# SCH_Endurance_drone_3.net
KiCad netlist of a schematic drawn in EasyEDA
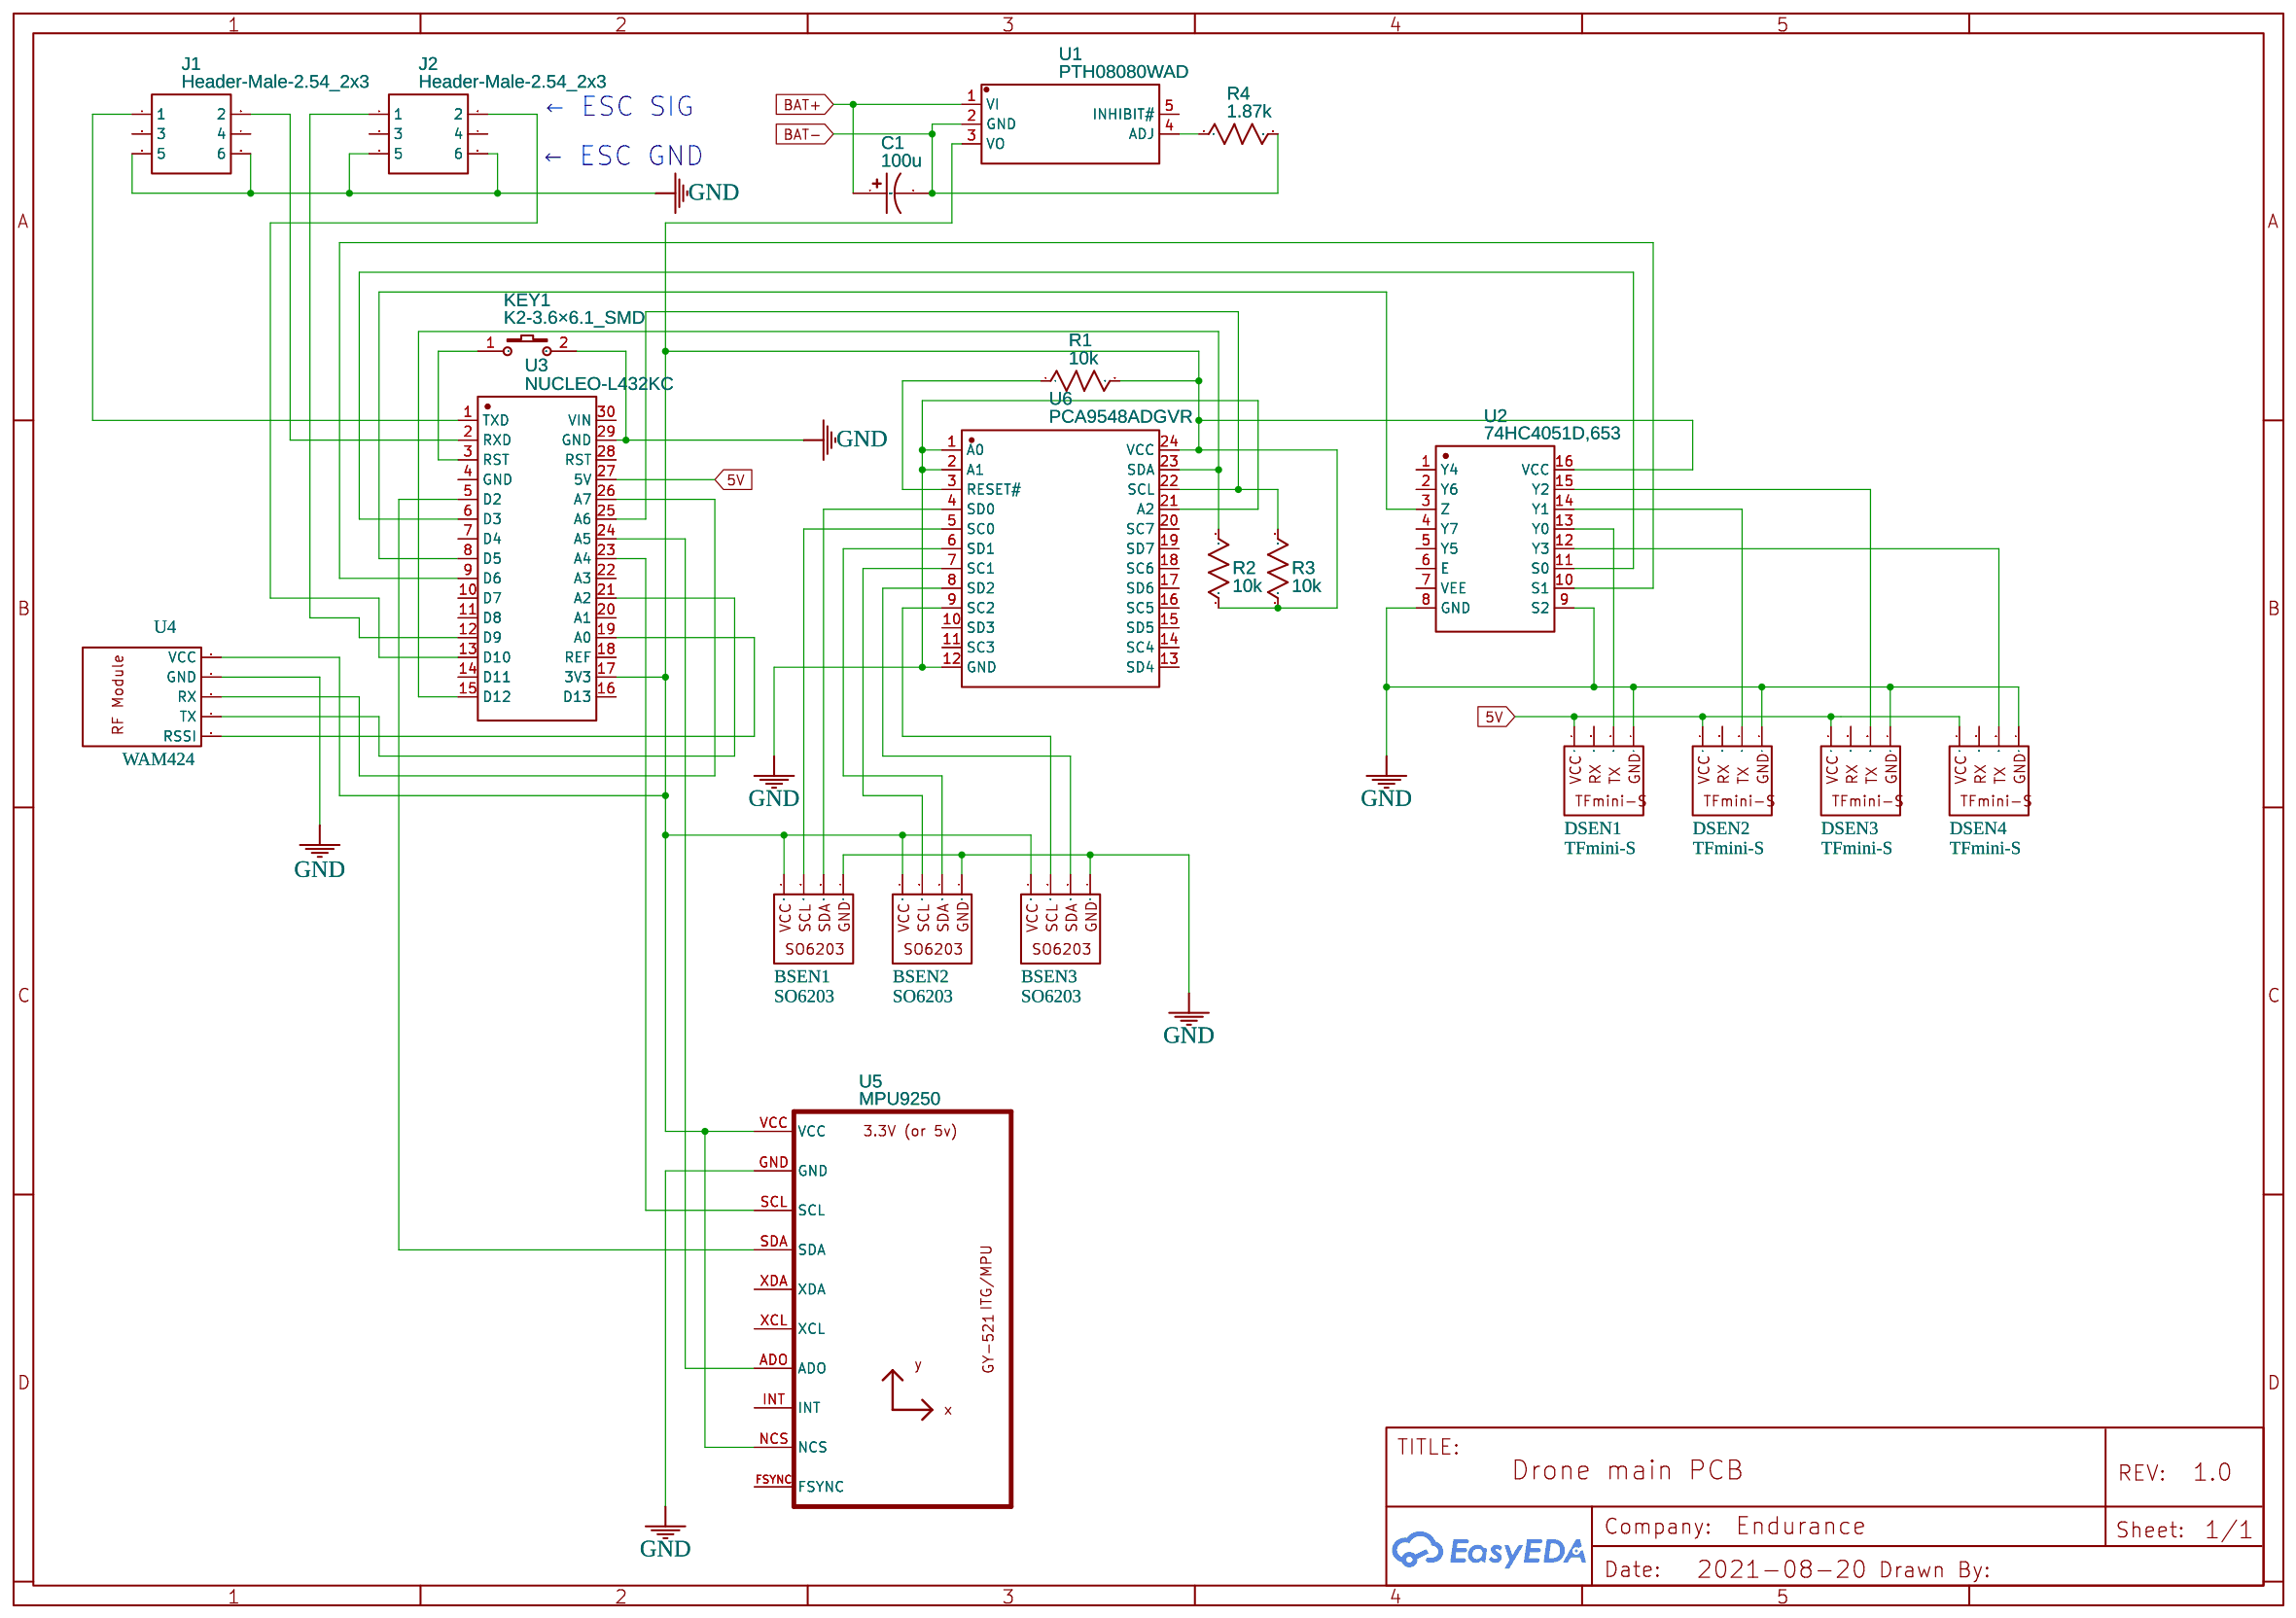
[diagram p0: schematic sheet]

(export (version "E")
  (design (tool "Eeschema 10.0.6"))
  (components
    (comp (ref "BSEN1") (value "SO6203") (libsource (lib "") (part "Unknown_405_-350")))
    (comp (ref "BSEN2") (value "SO6203") (libsource (lib "") (part "Unknown_465_-350")))
    (comp (ref "BSEN3") (value "SO6203") (libsource (lib "") (part "Unknown_530_-350")))
    (comp (ref "C1") (value "100u") (libsource (lib "") (part "C_Tan_SMD_A_US")))
    (comp (ref "DSEN1") (value "TFmini-S") (libsource (lib "") (part "Unknown_805_-425")))
    (comp (ref "DSEN2") (value "TFmini-S") (libsource (lib "") (part "Unknown_870_-425")))
    (comp (ref "DSEN3") (value "TFmini-S") (libsource (lib "") (part "Unknown_935_-425")))
    (comp (ref "DSEN4") (value "TFmini-S") (libsource (lib "") (part "Unknown_1000_-425")))
    (comp (ref "J1")
      (value "Header-Male-2.54_2x3")
      (fields (field (name "BOM_Supplier Part") "C65114"))
      (libsource (lib "") (part "Header-Male-2.54_2x3"))
    )
    (comp (ref "J2")
      (value "Header-Male-2.54_2x3")
      (fields (field (name "BOM_Supplier Part") "C65114"))
      (libsource (lib "") (part "Header-Male-2.54_2x3"))
    )
    (comp (ref "KEY1")
      (value "K2-3.6×6.1_SMD")
      (fields
        (field (name "BOM_Manufacturer Part") "K2-1107ST-A4SW-06")
        (field (name "BOM_Supplier Part") "C118141")
      )
      (libsource (lib "") (part "K2-3.6×6.1_SMD"))
    )
    (comp (ref "R1") (value "10k") (libsource (lib "") (part "R_0603_US_1")))
    (comp (ref "R2") (value "10k") (libsource (lib "") (part "R_0603_US")))
    (comp (ref "R3") (value "10k") (libsource (lib "") (part "R_0603_US")))
    (comp (ref "R4") (value "1.87k") (libsource (lib "") (part "R_0603_US_1")))
    (comp (ref "U1")
      (value "PTH08080WAD")
      (fields (field (name "BOM_Supplier Part") "C154927"))
      (libsource (lib "") (part "PTH08080WAD"))
    )
    (comp (ref "U2")
      (value "74HC4051D,653")
      (fields (field (name "BOM_Supplier Part") "C9386"))
      (libsource (lib "") (part "74HC4051D,653"))
    )
    (comp (ref "U3")
      (value "NUCLEO-L432KC")
      (fields (field (name "BOM_Supplier Part") "C94814"))
      (libsource (lib "") (part "NUCLEO-L432KC"))
    )
    (comp (ref "U4") (value "WAM424") (libsource (lib "") (part "Unknown_70_-460")))
    (comp (ref "U5") (value "MPU9250") (libsource (lib "") (part "MPU9250")))
    (comp (ref "U6")
      (value "PCA9548ADGVR")
      (fields (field (name "BOM_Supplier Part") "C2674421"))
      (libsource (lib "") (part "PCA9548ADGVR"))
    )
  )
  (nets
    (net (code "1") (name "5V") (class "Default")
      (node (ref "DSEN1") (pin "1") (pinfunction "1_1") (pintype "unspecified"))
      (node (ref "DSEN2") (pin "1") (pinfunction "1_1") (pintype "unspecified"))
      (node (ref "DSEN3") (pin "1") (pinfunction "1_1") (pintype "unspecified"))
      (node (ref "DSEN4") (pin "1") (pinfunction "1_1") (pintype "unspecified"))
      (node (ref "U3") (pin "27") (pinfunction "5V_27") (pintype "unspecified"))
    )
    (net (code "2") (name "BAT+") (class "Default")
      (node (ref "C1") (pin "1") (pinfunction "1_1") (pintype "unspecified"))
      (node (ref "U1") (pin "1") (pinfunction "VI_1") (pintype "unspecified"))
    )
    (net (code "3") (name "BAT-") (class "Default")
      (node (ref "C1") (pin "2") (pinfunction "2_2") (pintype "unspecified"))
      (node (ref "R4") (pin "2") (pinfunction "2_2") (pintype "unspecified"))
      (node (ref "U1") (pin "2") (pinfunction "GND_2") (pintype "unspecified"))
    )
    (net (code "4") (name "GND") (class "Default")
      (node (ref "BSEN1") (pin "4") (pinfunction "4_4") (pintype "unspecified"))
      (node (ref "BSEN2") (pin "4") (pinfunction "4_4") (pintype "unspecified"))
      (node (ref "BSEN3") (pin "4") (pinfunction "4_4") (pintype "unspecified"))
      (node (ref "DSEN1") (pin "4") (pinfunction "4_4") (pintype "unspecified"))
      (node (ref "DSEN2") (pin "4") (pinfunction "4_4") (pintype "unspecified"))
      (node (ref "DSEN3") (pin "4") (pinfunction "4_4") (pintype "unspecified"))
      (node (ref "DSEN4") (pin "4") (pinfunction "4_4") (pintype "unspecified"))
      (node (ref "J1") (pin "5") (pinfunction "5_5") (pintype "input"))
      (node (ref "J1") (pin "6") (pinfunction "6_6") (pintype "input"))
      (node (ref "J2") (pin "5") (pinfunction "5_5") (pintype "input"))
      (node (ref "J2") (pin "6") (pinfunction "6_6") (pintype "input"))
      (node (ref "KEY1") (pin "2") (pinfunction "2_2") (pintype "unspecified"))
      (node (ref "U2") (pin "8") (pinfunction "GND_8") (pintype "unspecified"))
      (node (ref "U2") (pin "9") (pinfunction "S2_9") (pintype "unspecified"))
      (node (ref "U3") (pin "29") (pinfunction "GND_29") (pintype "unspecified"))
      (node (ref "U4") (pin "2") (pinfunction "GND_2") (pintype "unspecified"))
      (node (ref "U5") (pin "GND") (pinfunction "GND_GND") (pintype "bidirectional"))
      (node (ref "U6") (pin "1") (pinfunction "A0_1") (pintype "unspecified"))
      (node (ref "U6") (pin "12") (pinfunction "GND_12") (pintype "unspecified"))
      (node (ref "U6") (pin "2") (pinfunction "A1_2") (pintype "unspecified"))
      (node (ref "U6") (pin "21") (pinfunction "A2_21") (pintype "unspecified"))
    )
    (net (code "5") (name "Net-(KEY1-Pad1)") (class "Default")
      (node (ref "KEY1") (pin "1") (pinfunction "1_1") (pintype "unspecified"))
      (node (ref "U3") (pin "3") (pinfunction "RST_3") (pintype "unspecified"))
    )
    (net (code "6") (name "Net-(U1-ADJ)") (class "Default")
      (node (ref "R4") (pin "1") (pinfunction "1_1") (pintype "unspecified"))
      (node (ref "U1") (pin "4") (pinfunction "ADJ_4") (pintype "unspecified"))
    )
    (net (code "7") (name "Net-(U1-VO)") (class "Default")
      (node (ref "BSEN1") (pin "1") (pinfunction "1_1") (pintype "unspecified"))
      (node (ref "BSEN2") (pin "1") (pinfunction "1_1") (pintype "unspecified"))
      (node (ref "BSEN3") (pin "1") (pinfunction "1_1") (pintype "unspecified"))
      (node (ref "R1") (pin "2") (pinfunction "2_2") (pintype "unspecified"))
      (node (ref "R2") (pin "1") (pinfunction "1_1") (pintype "unspecified"))
      (node (ref "R3") (pin "1") (pinfunction "1_1") (pintype "unspecified"))
      (node (ref "U1") (pin "3") (pinfunction "VO_3") (pintype "unspecified"))
      (node (ref "U2") (pin "16") (pinfunction "VCC_16") (pintype "unspecified"))
      (node (ref "U3") (pin "17") (pinfunction "3V3_17") (pintype "unspecified"))
      (node (ref "U4") (pin "1") (pinfunction "VCC_1") (pintype "unspecified"))
      (node (ref "U5") (pin "NCS") (pinfunction "NCS_NCS") (pintype "bidirectional"))
      (node (ref "U5") (pin "VCC") (pinfunction "VCC_VCC") (pintype "bidirectional"))
      (node (ref "U6") (pin "24") (pinfunction "VCC_24") (pintype "unspecified"))
    )
    (net (code "8") (name "Net-(U2-S0)") (class "Default")
      (node (ref "U2") (pin "11") (pinfunction "S0_11") (pintype "unspecified"))
      (node (ref "U3") (pin "6") (pinfunction "D3_6") (pintype "unspecified"))
    )
    (net (code "9") (name "Net-(U2-S1)") (class "Default")
      (node (ref "U2") (pin "10") (pinfunction "S1_10") (pintype "unspecified"))
      (node (ref "U3") (pin "9") (pinfunction "D6_9") (pintype "unspecified"))
    )
    (net (code "10") (name "Net-(U2-Y0)") (class "Default")
      (node (ref "DSEN1") (pin "3") (pinfunction "3_3") (pintype "unspecified"))
      (node (ref "U2") (pin "13") (pinfunction "Y0_13") (pintype "unspecified"))
    )
    (net (code "11") (name "Net-(U2-Y1)") (class "Default")
      (node (ref "DSEN2") (pin "3") (pinfunction "3_3") (pintype "unspecified"))
      (node (ref "U2") (pin "14") (pinfunction "Y1_14") (pintype "unspecified"))
    )
    (net (code "12") (name "Net-(U2-Y2)") (class "Default")
      (node (ref "DSEN3") (pin "3") (pinfunction "3_3") (pintype "unspecified"))
      (node (ref "U2") (pin "15") (pinfunction "Y2_15") (pintype "unspecified"))
    )
    (net (code "13") (name "Net-(U2-Y3)") (class "Default")
      (node (ref "DSEN4") (pin "3") (pinfunction "3_3") (pintype "unspecified"))
      (node (ref "U2") (pin "12") (pinfunction "Y3_12") (pintype "unspecified"))
    )
    (net (code "14") (name "Net-(U2-Z)") (class "Default")
      (node (ref "U2") (pin "3") (pinfunction "Z_3") (pintype "unspecified"))
      (node (ref "U3") (pin "8") (pinfunction "D5_8") (pintype "unspecified"))
    )
    (net (code "15") (name "Net-(U3-A0)") (class "Default")
      (node (ref "U3") (pin "19") (pinfunction "A0_19") (pintype "unspecified"))
      (node (ref "U4") (pin "5") (pinfunction "RSSI_5") (pintype "unspecified"))
    )
    (net (code "16") (name "Net-(U3-A2)") (class "Default")
      (node (ref "U3") (pin "21") (pinfunction "A2_21") (pintype "unspecified"))
      (node (ref "U4") (pin "4") (pinfunction "TX_4") (pintype "unspecified"))
    )
    (net (code "17") (name "Net-(U3-A4)") (class "Default")
      (node (ref "U3") (pin "23") (pinfunction "A4_23") (pintype "unspecified"))
      (node (ref "U5") (pin "SCL") (pinfunction "SCL_SCL") (pintype "bidirectional"))
    )
    (net (code "18") (name "Net-(U3-A5)") (class "Default")
      (node (ref "U3") (pin "24") (pinfunction "A5_24") (pintype "unspecified"))
      (node (ref "U5") (pin "ADO") (pinfunction "ADO_ADO") (pintype "bidirectional"))
    )
    (net (code "19") (name "Net-(U3-A6)") (class "Default")
      (node (ref "R3") (pin "2") (pinfunction "2_2") (pintype "unspecified"))
      (node (ref "U3") (pin "25") (pinfunction "A6_25") (pintype "unspecified"))
      (node (ref "U6") (pin "22") (pinfunction "SCL_22") (pintype "unspecified"))
    )
    (net (code "20") (name "Net-(U3-A7)") (class "Default")
      (node (ref "U3") (pin "26") (pinfunction "A7_26") (pintype "unspecified"))
      (node (ref "U4") (pin "3") (pinfunction "RX_3") (pintype "unspecified"))
    )
    (net (code "21") (name "Net-(U3-D2)") (class "Default")
      (node (ref "U3") (pin "5") (pinfunction "D2_5") (pintype "unspecified"))
      (node (ref "U5") (pin "SDA") (pinfunction "SDA_SDA") (pintype "bidirectional"))
    )
    (net (code "22") (name "Net-(U3-D9)") (class "Default")
      (node (ref "J2") (pin "1") (pinfunction "1_1") (pintype "input"))
      (node (ref "U3") (pin "12") (pinfunction "D9_12") (pintype "unspecified"))
    )
    (net (code "23") (name "Net-(U3-D10)") (class "Default")
      (node (ref "J2") (pin "2") (pinfunction "2_2") (pintype "input"))
      (node (ref "U3") (pin "13") (pinfunction "D10_13") (pintype "unspecified"))
    )
    (net (code "24") (name "Net-(U3-D12)") (class "Default")
      (node (ref "R2") (pin "2") (pinfunction "2_2") (pintype "unspecified"))
      (node (ref "U3") (pin "15") (pinfunction "D12_15") (pintype "unspecified"))
      (node (ref "U6") (pin "23") (pinfunction "SDA_23") (pintype "unspecified"))
    )
    (net (code "25") (name "Net-(U3-RXD)") (class "Default")
      (node (ref "J1") (pin "2") (pinfunction "2_2") (pintype "input"))
      (node (ref "U3") (pin "2") (pinfunction "RXD_2") (pintype "unspecified"))
    )
    (net (code "26") (name "Net-(U3-TXD)") (class "Default")
      (node (ref "J1") (pin "1") (pinfunction "1_1") (pintype "input"))
      (node (ref "U3") (pin "1") (pinfunction "TXD_1") (pintype "unspecified"))
    )
    (net (code "27") (name "Net-(U6-RESET#)") (class "Default")
      (node (ref "R1") (pin "1") (pinfunction "1_1") (pintype "unspecified"))
      (node (ref "U6") (pin "3") (pinfunction "RESET#_3") (pintype "unspecified"))
    )
    (net (code "28") (name "Net-(U6-SC0)") (class "Default")
      (node (ref "BSEN1") (pin "2") (pinfunction "2_2") (pintype "unspecified"))
      (node (ref "U6") (pin "5") (pinfunction "SC0_5") (pintype "unspecified"))
    )
    (net (code "29") (name "Net-(U6-SC1)") (class "Default")
      (node (ref "BSEN2") (pin "2") (pinfunction "2_2") (pintype "unspecified"))
      (node (ref "U6") (pin "7") (pinfunction "SC1_7") (pintype "unspecified"))
    )
    (net (code "30") (name "Net-(U6-SC2)") (class "Default")
      (node (ref "BSEN3") (pin "2") (pinfunction "2_2") (pintype "unspecified"))
      (node (ref "U6") (pin "9") (pinfunction "SC2_9") (pintype "unspecified"))
    )
    (net (code "31") (name "Net-(U6-SD0)") (class "Default")
      (node (ref "BSEN1") (pin "3") (pinfunction "3_3") (pintype "unspecified"))
      (node (ref "U6") (pin "4") (pinfunction "SD0_4") (pintype "unspecified"))
    )
    (net (code "32") (name "Net-(U6-SD1)") (class "Default")
      (node (ref "BSEN2") (pin "3") (pinfunction "3_3") (pintype "unspecified"))
      (node (ref "U6") (pin "6") (pinfunction "SD1_6") (pintype "unspecified"))
    )
    (net (code "33") (name "Net-(U6-SD2)") (class "Default")
      (node (ref "BSEN3") (pin "3") (pinfunction "3_3") (pintype "unspecified"))
      (node (ref "U6") (pin "8") (pinfunction "SD2_8") (pintype "unspecified"))
    )
    (net (code "34") (name "unconnected-(DSEN1-Pad2)") (class "Default")
      (node (ref "DSEN1") (pin "2") (pinfunction "2_2") (pintype "unspecified"))
    )
    (net (code "35") (name "unconnected-(DSEN2-Pad2)") (class "Default")
      (node (ref "DSEN2") (pin "2") (pinfunction "2_2") (pintype "unspecified"))
    )
    (net (code "36") (name "unconnected-(DSEN3-Pad2)") (class "Default")
      (node (ref "DSEN3") (pin "2") (pinfunction "2_2") (pintype "unspecified"))
    )
    (net (code "37") (name "unconnected-(DSEN4-Pad2)") (class "Default")
      (node (ref "DSEN4") (pin "2") (pinfunction "2_2") (pintype "unspecified"))
    )
    (net (code "38") (name "unconnected-(J1-Pad3)") (class "Default")
      (node (ref "J1") (pin "3") (pinfunction "3_3") (pintype "input"))
    )
    (net (code "39") (name "unconnected-(J1-Pad4)") (class "Default")
      (node (ref "J1") (pin "4") (pinfunction "4_4") (pintype "input"))
    )
    (net (code "40") (name "unconnected-(J2-Pad3)") (class "Default")
      (node (ref "J2") (pin "3") (pinfunction "3_3") (pintype "input"))
    )
    (net (code "41") (name "unconnected-(J2-Pad4)") (class "Default")
      (node (ref "J2") (pin "4") (pinfunction "4_4") (pintype "input"))
    )
    (net (code "42") (name "unconnected-(U1-INHIBIT#-Pad5)") (class "Default")
      (node (ref "U1") (pin "5") (pinfunction "INHIBIT#_5") (pintype "unspecified"))
    )
    (net (code "43") (name "unconnected-(U2-E-Pad6)") (class "Default")
      (node (ref "U2") (pin "6") (pinfunction "E_6") (pintype "unspecified"))
    )
    (net (code "44") (name "unconnected-(U2-VEE-Pad7)") (class "Default")
      (node (ref "U2") (pin "7") (pinfunction "VEE_7") (pintype "unspecified"))
    )
    (net (code "45") (name "unconnected-(U2-Y4-Pad1)") (class "Default")
      (node (ref "U2") (pin "1") (pinfunction "Y4_1") (pintype "unspecified"))
    )
    (net (code "46") (name "unconnected-(U2-Y5-Pad5)") (class "Default")
      (node (ref "U2") (pin "5") (pinfunction "Y5_5") (pintype "unspecified"))
    )
    (net (code "47") (name "unconnected-(U2-Y6-Pad2)") (class "Default")
      (node (ref "U2") (pin "2") (pinfunction "Y6_2") (pintype "unspecified"))
    )
    (net (code "48") (name "unconnected-(U2-Y7-Pad4)") (class "Default")
      (node (ref "U2") (pin "4") (pinfunction "Y7_4") (pintype "unspecified"))
    )
    (net (code "49") (name "unconnected-(U3-A1-Pad20)") (class "Default")
      (node (ref "U3") (pin "20") (pinfunction "A1_20") (pintype "unspecified"))
    )
    (net (code "50") (name "unconnected-(U3-A3-Pad22)") (class "Default")
      (node (ref "U3") (pin "22") (pinfunction "A3_22") (pintype "unspecified"))
    )
    (net (code "51") (name "unconnected-(U3-D4-Pad7)") (class "Default")
      (node (ref "U3") (pin "7") (pinfunction "D4_7") (pintype "unspecified"))
    )
    (net (code "52") (name "unconnected-(U3-D7-Pad10)") (class "Default")
      (node (ref "U3") (pin "10") (pinfunction "D7_10") (pintype "unspecified"))
    )
    (net (code "53") (name "unconnected-(U3-D8-Pad11)") (class "Default")
      (node (ref "U3") (pin "11") (pinfunction "D8_11") (pintype "unspecified"))
    )
    (net (code "54") (name "unconnected-(U3-D11-Pad14)") (class "Default")
      (node (ref "U3") (pin "14") (pinfunction "D11_14") (pintype "unspecified"))
    )
    (net (code "55") (name "unconnected-(U3-D13-Pad16)") (class "Default")
      (node (ref "U3") (pin "16") (pinfunction "D13_16") (pintype "unspecified"))
    )
    (net (code "56") (name "unconnected-(U3-GND-Pad4)") (class "Default")
      (node (ref "U3") (pin "4") (pinfunction "GND_4") (pintype "unspecified"))
    )
    (net (code "57") (name "unconnected-(U3-REF-Pad18)") (class "Default")
      (node (ref "U3") (pin "18") (pinfunction "REF_18") (pintype "unspecified"))
    )
    (net (code "58") (name "unconnected-(U3-RST-Pad28)") (class "Default")
      (node (ref "U3") (pin "28") (pinfunction "RST_28") (pintype "unspecified"))
    )
    (net (code "59") (name "unconnected-(U3-VIN-Pad30)") (class "Default")
      (node (ref "U3") (pin "30") (pinfunction "VIN_30") (pintype "unspecified"))
    )
    (net (code "60") (name "unconnected-(U5-PadFSYNC)") (class "Default")
      (node (ref "U5") (pin "FSYNC") (pinfunction "FSYNC_FSYNC") (pintype "bidirectional"))
    )
    (net (code "61") (name "unconnected-(U5-PadINT)") (class "Default")
      (node (ref "U5") (pin "INT") (pinfunction "INT_INT") (pintype "bidirectional"))
    )
    (net (code "62") (name "unconnected-(U5-PadXCL)") (class "Default")
      (node (ref "U5") (pin "XCL") (pinfunction "XCL_XCL") (pintype "bidirectional"))
    )
    (net (code "63") (name "unconnected-(U5-PadXDA)") (class "Default")
      (node (ref "U5") (pin "XDA") (pinfunction "XDA_XDA") (pintype "bidirectional"))
    )
    (net (code "64") (name "unconnected-(U6-SC3-Pad11)") (class "Default")
      (node (ref "U6") (pin "11") (pinfunction "SC3_11") (pintype "unspecified"))
    )
    (net (code "65") (name "unconnected-(U6-SC4-Pad14)") (class "Default")
      (node (ref "U6") (pin "14") (pinfunction "SC4_14") (pintype "unspecified"))
    )
    (net (code "66") (name "unconnected-(U6-SC5-Pad16)") (class "Default")
      (node (ref "U6") (pin "16") (pinfunction "SC5_16") (pintype "unspecified"))
    )
    (net (code "67") (name "unconnected-(U6-SC6-Pad18)") (class "Default")
      (node (ref "U6") (pin "18") (pinfunction "SC6_18") (pintype "unspecified"))
    )
    (net (code "68") (name "unconnected-(U6-SC7-Pad20)") (class "Default")
      (node (ref "U6") (pin "20") (pinfunction "SC7_20") (pintype "unspecified"))
    )
    (net (code "69") (name "unconnected-(U6-SD3-Pad10)") (class "Default")
      (node (ref "U6") (pin "10") (pinfunction "SD3_10") (pintype "unspecified"))
    )
    (net (code "70") (name "unconnected-(U6-SD4-Pad13)") (class "Default")
      (node (ref "U6") (pin "13") (pinfunction "SD4_13") (pintype "unspecified"))
    )
    (net (code "71") (name "unconnected-(U6-SD5-Pad15)") (class "Default")
      (node (ref "U6") (pin "15") (pinfunction "SD5_15") (pintype "unspecified"))
    )
    (net (code "72") (name "unconnected-(U6-SD6-Pad17)") (class "Default")
      (node (ref "U6") (pin "17") (pinfunction "SD6_17") (pintype "unspecified"))
    )
    (net (code "73") (name "unconnected-(U6-SD7-Pad19)") (class "Default")
      (node (ref "U6") (pin "19") (pinfunction "SD7_19") (pintype "unspecified"))
    )
  )
)
